# DAC.net
KiCad netlist of a schematic drawn in Altium Designer
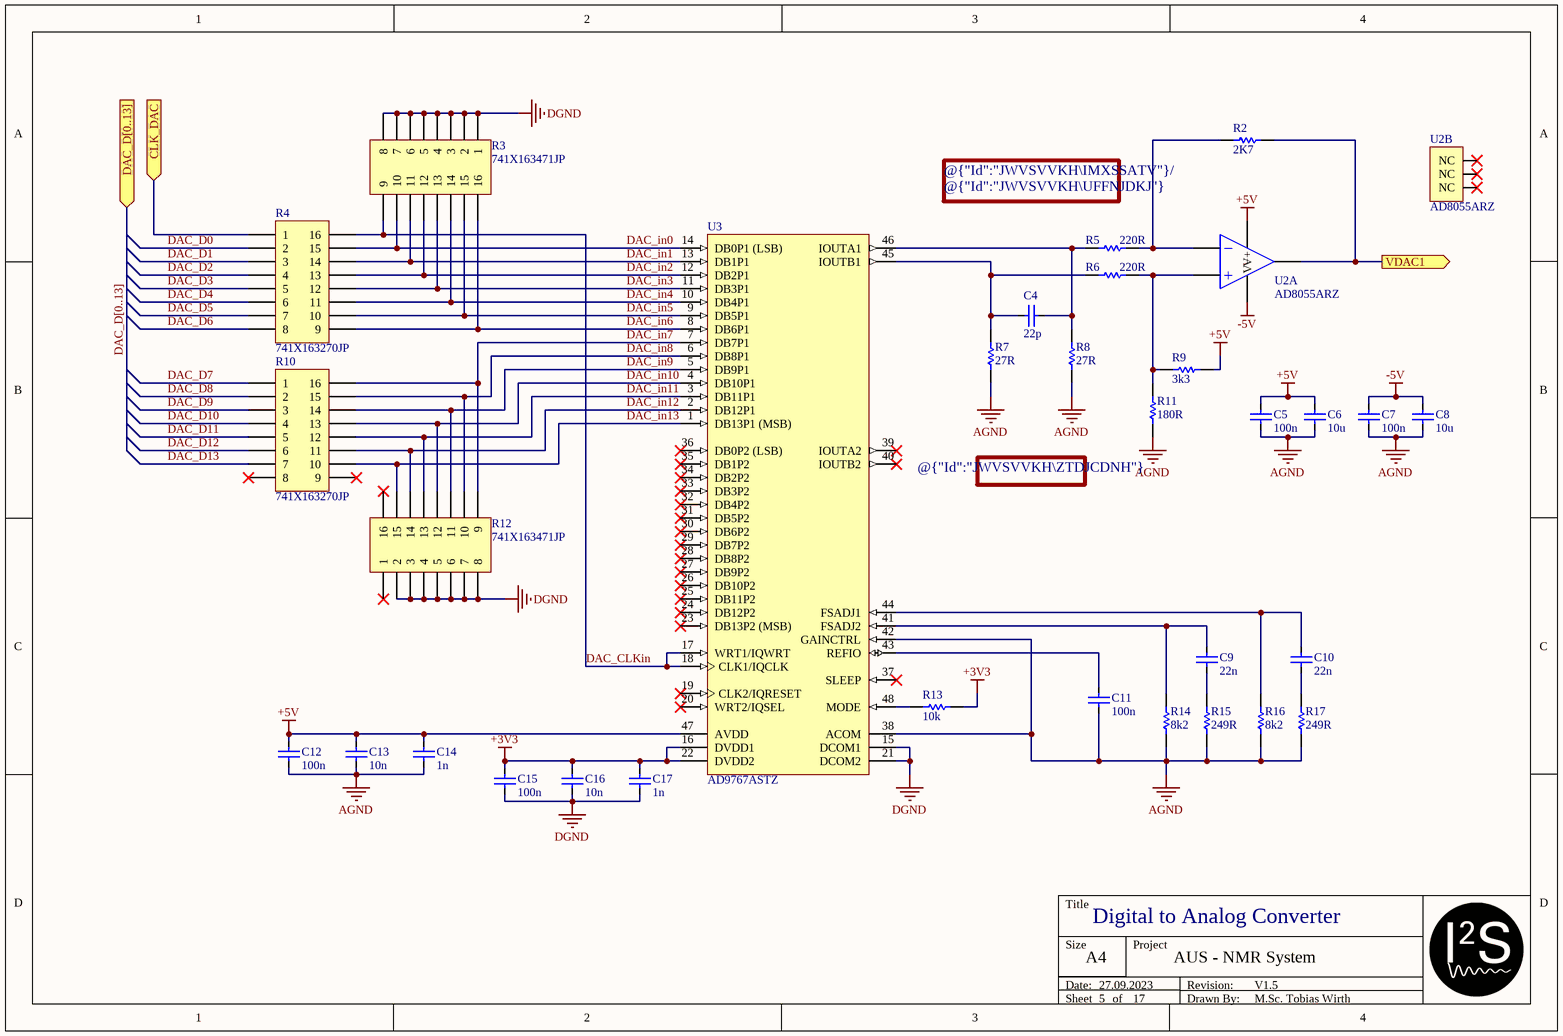
[diagram p0: DAC.SchDoc]

(export (version "E")
  (design (tool "Eeschema 10.0.6"))
  (components
    (comp (ref "C4") (value "22p") (footprint "CAP_0402") (libsource (lib "IIS-Lib_TW") (part "Cap")))
    (comp (ref "C5") (value "100n") (footprint "CAP_0402") (libsource (lib "IIS-Lib_TW") (part "Cap")))
    (comp (ref "C6") (value "10u") (footprint "CAP_0603") (libsource (lib "IIS-Lib_TW") (part "Cap")))
    (comp (ref "C7") (value "100n") (footprint "CAP_0402") (libsource (lib "IIS-Lib_TW") (part "Cap")))
    (comp (ref "C8") (value "10u") (footprint "CAP_0603") (libsource (lib "IIS-Lib_TW") (part "Cap")))
    (comp (ref "C9") (value "22n") (footprint "CAP_0402") (libsource (lib "IIS-Lib_TW") (part "Cap")))
    (comp (ref "C10") (value "22n") (footprint "CAP_0402") (libsource (lib "IIS-Lib_TW") (part "Cap")))
    (comp (ref "C11") (value "100n") (footprint "CAP_0402") (libsource (lib "IIS-Lib_TW") (part "Cap")))
    (comp (ref "C12") (value "100n") (footprint "CAP_0402") (libsource (lib "IIS-Lib_TW") (part "Cap")))
    (comp (ref "C13") (value "10n") (footprint "CAP_0402") (libsource (lib "IIS-Lib_TW") (part "Cap")))
    (comp (ref "C14") (value "1n") (footprint "CAP_0402") (libsource (lib "IIS-Lib_TW") (part "Cap")))
    (comp (ref "C15") (value "100n") (footprint "CAP_0402") (libsource (lib "IIS-Lib_TW") (part "Cap")))
    (comp (ref "C16") (value "10n") (footprint "CAP_0402") (libsource (lib "IIS-Lib_TW") (part "Cap")))
    (comp (ref "C17") (value "1n") (footprint "CAP_0402") (libsource (lib "IIS-Lib_TW") (part "Cap")))
    (comp (ref "R2") (value "2K7") (footprint "RES_0402") (libsource (lib "IIS-Lib_TW") (part "Res")))
    (comp (ref "R3")
      (value "741X163471JP")
      (footprint "741X163")
      (description "Isolated 8 Resistor Network/Array, Convex, Long Side Terminals")
      (libsource (lib "") (part "741X163_2"))
    )
    (comp (ref "R4")
      (value "741X163270JP")
      (footprint "741X163")
      (description "Isolated 8 Resistor Network/Array, Convex, Long Side Terminals")
      (libsource (lib "IIS-Lib_TW") (part "741X163"))
    )
    (comp (ref "R5") (value "220R") (footprint "RES_0402") (libsource (lib "IIS-Lib_TW") (part "Res")))
    (comp (ref "R6") (value "220R") (footprint "RES_0402") (libsource (lib "IIS-Lib_TW") (part "Res")))
    (comp (ref "R7") (value "27R") (footprint "RES_0402") (libsource (lib "IIS-Lib_TW") (part "Res")))
    (comp (ref "R8") (value "27R") (footprint "RES_0402") (libsource (lib "IIS-Lib_TW") (part "Res")))
    (comp (ref "R9") (value "3k3") (footprint "RES_0402") (libsource (lib "IIS-Lib_TW") (part "Res")))
    (comp (ref "R10")
      (value "741X163270JP")
      (footprint "741X163")
      (description "Isolated 8 Resistor Network/Array, Convex, Long Side Terminals")
      (libsource (lib "IIS-Lib_TW") (part "741X163"))
    )
    (comp (ref "R11") (value "180R") (footprint "RES_0402") (libsource (lib "IIS-Lib_TW") (part "Res")))
    (comp (ref "R12")
      (value "741X163471JP")
      (footprint "741X163")
      (description "Isolated 8 Resistor Network/Array, Convex, Long Side Terminals")
      (libsource (lib "") (part "741X163_1"))
    )
    (comp (ref "R13") (value "10k") (footprint "RES_0402") (libsource (lib "IIS-Lib_TW") (part "Res")))
    (comp (ref "R14") (value "8k2") (footprint "RES_0402") (libsource (lib "IIS-Lib_TW") (part "Res")))
    (comp (ref "R15") (value "249R") (footprint "RES_0402") (libsource (lib "IIS-Lib_TW") (part "Res")))
    (comp (ref "R16") (value "8k2") (footprint "RES_0402") (libsource (lib "IIS-Lib_TW") (part "Res")))
    (comp (ref "R17") (value "249R") (footprint "RES_0402") (libsource (lib "IIS-Lib_TW") (part "Res")))
    (comp (ref "U2")
      (value "AD8055ARZ")
      (footprint "SOIC127P600X175-8N")
      (description "300 MHz Voltage Feedback Amplifier")
      (libsource (lib "IIS-Lib_TW") (part "AD8055"))
    )
    (comp (ref "U3")
      (value "AD9767ASTZ")
      (footprint "TQFP-48_L")
      (description "Dual 14-Bit TxDAC+, 125 Msps, -40 to +85 degC, ST-48, Pb-Free, Tray")
      (fields (field (name "GENERIC PART NUMBER") "AD9767") (field (name "MANUFACTURER") "Analog Devices"))
      (libsource (lib "IIS-Lib_TW") (part "AD9767"))
    )
  )
  (nets
    (net (code "1") (name "+3V3") (class "Default")
      (node (ref "C15") (pin "1") (pinfunction "1_1") (pintype "passive"))
      (node (ref "C16") (pin "1") (pinfunction "1_1") (pintype "passive"))
      (node (ref "C17") (pin "1") (pinfunction "1_1") (pintype "passive"))
      (node (ref "R13") (pin "1") (pinfunction "1_1") (pintype "passive"))
      (node (ref "U3") (pin "16") (pinfunction "DVDD1_16") (pintype "power_in"))
      (node (ref "U3") (pin "22") (pinfunction "DVDD2_22") (pintype "power_in"))
    )
    (net (code "2") (name "+5V") (class "Default")
      (node (ref "C12") (pin "1") (pinfunction "1_1") (pintype "passive"))
      (node (ref "C13") (pin "1") (pinfunction "1_1") (pintype "passive"))
      (node (ref "C14") (pin "1") (pinfunction "1_1") (pintype "passive"))
      (node (ref "C5") (pin "1") (pinfunction "1_1") (pintype "passive"))
      (node (ref "C6") (pin "1") (pinfunction "1_1") (pintype "passive"))
      (node (ref "R9") (pin "1") (pinfunction "1_1") (pintype "passive"))
      (node (ref "U2") (pin "7") (pinfunction "V+_7") (pintype "passive"))
      (node (ref "U3") (pin "47") (pinfunction "AVDD_47") (pintype "power_in"))
    )
    (net (code "3") (name "-5V") (class "Default")
      (node (ref "C7") (pin "1") (pinfunction "1_1") (pintype "passive"))
      (node (ref "C8") (pin "1") (pinfunction "1_1") (pintype "passive"))
      (node (ref "U2") (pin "4") (pinfunction "V−_4") (pintype "passive"))
    )
    (net (code "5") (name "/CLK_DAC") (class "Default")
      (node (ref "R4") (pin "1") (pinfunction "1_1") (pintype "passive"))
    )
    (net (code "6") (name "/DAC_CLKin") (class "Default")
      (node (ref "R3") (pin "9") (pinfunction "9_9") (pintype "passive"))
      (node (ref "R4") (pin "16") (pinfunction "16_16") (pintype "passive"))
      (node (ref "U3") (pin "17") (pinfunction "WRT1/IQWRT_17") (pintype "input"))
      (node (ref "U3") (pin "18") (pinfunction "CLK1/IQCLK_18") (pintype "input"))
    )
    (net (code "7") (name "/DAC_D0") (class "Default")
      (node (ref "R4") (pin "2") (pinfunction "2_2") (pintype "passive"))
    )
    (net (code "8") (name "/DAC_D1") (class "Default")
      (node (ref "R4") (pin "3") (pinfunction "3_3") (pintype "passive"))
    )
    (net (code "9") (name "/DAC_D2") (class "Default")
      (node (ref "R4") (pin "4") (pinfunction "4_4") (pintype "passive"))
    )
    (net (code "10") (name "/DAC_D3") (class "Default")
      (node (ref "R4") (pin "5") (pinfunction "5_5") (pintype "passive"))
    )
    (net (code "11") (name "/DAC_D4") (class "Default")
      (node (ref "R4") (pin "6") (pinfunction "6_6") (pintype "passive"))
    )
    (net (code "12") (name "/DAC_D5") (class "Default")
      (node (ref "R4") (pin "7") (pinfunction "7_7") (pintype "passive"))
    )
    (net (code "13") (name "/DAC_D6") (class "Default")
      (node (ref "R4") (pin "8") (pinfunction "8_8") (pintype "passive"))
    )
    (net (code "14") (name "/DAC_D7") (class "Default")
      (node (ref "R10") (pin "1") (pinfunction "1_1") (pintype "passive"))
    )
    (net (code "15") (name "/DAC_D8") (class "Default")
      (node (ref "R10") (pin "2") (pinfunction "2_2") (pintype "passive"))
    )
    (net (code "16") (name "/DAC_D9") (class "Default")
      (node (ref "R10") (pin "3") (pinfunction "3_3") (pintype "passive"))
    )
    (net (code "17") (name "/DAC_D10") (class "Default")
      (node (ref "R10") (pin "4") (pinfunction "4_4") (pintype "passive"))
    )
    (net (code "18") (name "/DAC_D11") (class "Default")
      (node (ref "R10") (pin "5") (pinfunction "5_5") (pintype "passive"))
    )
    (net (code "19") (name "/DAC_D12") (class "Default")
      (node (ref "R10") (pin "6") (pinfunction "6_6") (pintype "passive"))
    )
    (net (code "20") (name "/DAC_D13") (class "Default")
      (node (ref "R10") (pin "7") (pinfunction "7_7") (pintype "passive"))
    )
    (net (code "22") (name "/DAC_in0") (class "Default")
      (node (ref "R3") (pin "10") (pinfunction "10_10") (pintype "passive"))
      (node (ref "R4") (pin "15") (pinfunction "15_15") (pintype "passive"))
      (node (ref "U3") (pin "14") (pinfunction "DB0P1_(LSB)_14") (pintype "input"))
    )
    (net (code "23") (name "/DAC_in1") (class "Default")
      (node (ref "R3") (pin "11") (pinfunction "11_11") (pintype "passive"))
      (node (ref "R4") (pin "14") (pinfunction "14_14") (pintype "passive"))
      (node (ref "U3") (pin "13") (pinfunction "DB1P1_13") (pintype "input"))
    )
    (net (code "24") (name "/DAC_in2") (class "Default")
      (node (ref "R3") (pin "12") (pinfunction "12_12") (pintype "passive"))
      (node (ref "R4") (pin "13") (pinfunction "13_13") (pintype "passive"))
      (node (ref "U3") (pin "12") (pinfunction "DB2P1_12") (pintype "input"))
    )
    (net (code "25") (name "/DAC_in3") (class "Default")
      (node (ref "R3") (pin "13") (pinfunction "13_13") (pintype "passive"))
      (node (ref "R4") (pin "12") (pinfunction "12_12") (pintype "passive"))
      (node (ref "U3") (pin "11") (pinfunction "DB3P1_11") (pintype "input"))
    )
    (net (code "26") (name "/DAC_in4") (class "Default")
      (node (ref "R3") (pin "14") (pinfunction "14_14") (pintype "passive"))
      (node (ref "R4") (pin "11") (pinfunction "11_11") (pintype "passive"))
      (node (ref "U3") (pin "10") (pinfunction "DB4P1_10") (pintype "input"))
    )
    (net (code "27") (name "/DAC_in5") (class "Default")
      (node (ref "R3") (pin "15") (pinfunction "15_15") (pintype "passive"))
      (node (ref "R4") (pin "10") (pinfunction "10_10") (pintype "passive"))
      (node (ref "U3") (pin "9") (pinfunction "DB5P1_9") (pintype "input"))
    )
    (net (code "28") (name "/DAC_in6") (class "Default")
      (node (ref "R3") (pin "16") (pinfunction "16_16") (pintype "passive"))
      (node (ref "R4") (pin "9") (pinfunction "9_9") (pintype "passive"))
      (node (ref "U3") (pin "8") (pinfunction "DB6P1_8") (pintype "input"))
    )
    (net (code "29") (name "/DAC_in7") (class "Default")
      (node (ref "R10") (pin "16") (pinfunction "16_16") (pintype "passive"))
      (node (ref "R12") (pin "9") (pinfunction "9_9") (pintype "passive"))
      (node (ref "U3") (pin "7") (pinfunction "DB7P1_7") (pintype "input"))
    )
    (net (code "30") (name "/DAC_in8") (class "Default")
      (node (ref "R10") (pin "15") (pinfunction "15_15") (pintype "passive"))
      (node (ref "R12") (pin "10") (pinfunction "10_10") (pintype "passive"))
      (node (ref "U3") (pin "6") (pinfunction "DB8P1_6") (pintype "input"))
    )
    (net (code "31") (name "/DAC_in9") (class "Default")
      (node (ref "R10") (pin "14") (pinfunction "14_14") (pintype "passive"))
      (node (ref "R12") (pin "11") (pinfunction "11_11") (pintype "passive"))
      (node (ref "U3") (pin "5") (pinfunction "DB9P1_5") (pintype "input"))
    )
    (net (code "32") (name "/DAC_in10") (class "Default")
      (node (ref "R10") (pin "13") (pinfunction "13_13") (pintype "passive"))
      (node (ref "R12") (pin "12") (pinfunction "12_12") (pintype "passive"))
      (node (ref "U3") (pin "4") (pinfunction "DB10P1_4") (pintype "input"))
    )
    (net (code "33") (name "/DAC_in11") (class "Default")
      (node (ref "R10") (pin "12") (pinfunction "12_12") (pintype "passive"))
      (node (ref "R12") (pin "13") (pinfunction "13_13") (pintype "passive"))
      (node (ref "U3") (pin "3") (pinfunction "DB11P1_3") (pintype "input"))
    )
    (net (code "34") (name "/DAC_in12") (class "Default")
      (node (ref "R10") (pin "11") (pinfunction "11_11") (pintype "passive"))
      (node (ref "R12") (pin "14") (pinfunction "14_14") (pintype "passive"))
      (node (ref "U3") (pin "2") (pinfunction "DB12P1_2") (pintype "input"))
    )
    (net (code "35") (name "/DAC_in13") (class "Default")
      (node (ref "R10") (pin "10") (pinfunction "10_10") (pintype "passive"))
      (node (ref "R12") (pin "15") (pinfunction "15_15") (pintype "passive"))
      (node (ref "U3") (pin "1") (pinfunction "DB13P1_(MSB)_1") (pintype "input"))
    )
    (net (code "36") (name "/VDAC1") (class "Default")
      (node (ref "R2") (pin "2") (pinfunction "2_2") (pintype "passive"))
      (node (ref "U2") (pin "6") (pinfunction "6_6") (pintype "passive"))
    )
    (net (code "37") (name "AGND") (class "Default")
      (node (ref "C11") (pin "2") (pinfunction "2_2") (pintype "passive"))
      (node (ref "C12") (pin "2") (pinfunction "2_2") (pintype "passive"))
      (node (ref "C13") (pin "2") (pinfunction "2_2") (pintype "passive"))
      (node (ref "C14") (pin "2") (pinfunction "2_2") (pintype "passive"))
      (node (ref "C5") (pin "2") (pinfunction "2_2") (pintype "passive"))
      (node (ref "C6") (pin "2") (pinfunction "2_2") (pintype "passive"))
      (node (ref "C7") (pin "2") (pinfunction "2_2") (pintype "passive"))
      (node (ref "C8") (pin "2") (pinfunction "2_2") (pintype "passive"))
      (node (ref "R11") (pin "1") (pinfunction "1_1") (pintype "passive"))
      (node (ref "R14") (pin "1") (pinfunction "1_1") (pintype "passive"))
      (node (ref "R15") (pin "1") (pinfunction "1_1") (pintype "passive"))
      (node (ref "R16") (pin "1") (pinfunction "1_1") (pintype "passive"))
      (node (ref "R17") (pin "1") (pinfunction "1_1") (pintype "passive"))
      (node (ref "R7") (pin "1") (pinfunction "1_1") (pintype "passive"))
      (node (ref "R8") (pin "1") (pinfunction "1_1") (pintype "passive"))
      (node (ref "U3") (pin "38") (pinfunction "ACOM_38") (pintype "power_in"))
      (node (ref "U3") (pin "42") (pinfunction "GAINCTRL_42") (pintype "input"))
    )
    (net (code "38") (name "DGND") (class "Default")
      (node (ref "C15") (pin "2") (pinfunction "2_2") (pintype "passive"))
      (node (ref "C16") (pin "2") (pinfunction "2_2") (pintype "passive"))
      (node (ref "C17") (pin "2") (pinfunction "2_2") (pintype "passive"))
      (node (ref "R12") (pin "2") (pinfunction "2_2") (pintype "passive"))
      (node (ref "R12") (pin "3") (pinfunction "3_3") (pintype "passive"))
      (node (ref "R12") (pin "4") (pinfunction "4_4") (pintype "passive"))
      (node (ref "R12") (pin "5") (pinfunction "5_5") (pintype "passive"))
      (node (ref "R12") (pin "6") (pinfunction "6_6") (pintype "passive"))
      (node (ref "R12") (pin "7") (pinfunction "7_7") (pintype "passive"))
      (node (ref "R12") (pin "8") (pinfunction "8_8") (pintype "passive"))
      (node (ref "R3") (pin "1") (pinfunction "1_1") (pintype "passive"))
      (node (ref "R3") (pin "2") (pinfunction "2_2") (pintype "passive"))
      (node (ref "R3") (pin "3") (pinfunction "3_3") (pintype "passive"))
      (node (ref "R3") (pin "4") (pinfunction "4_4") (pintype "passive"))
      (node (ref "R3") (pin "5") (pinfunction "5_5") (pintype "passive"))
      (node (ref "R3") (pin "6") (pinfunction "6_6") (pintype "passive"))
      (node (ref "R3") (pin "7") (pinfunction "7_7") (pintype "passive"))
      (node (ref "R3") (pin "8") (pinfunction "8_8") (pintype "passive"))
      (node (ref "U3") (pin "15") (pinfunction "DCOM1_15") (pintype "power_in"))
      (node (ref "U3") (pin "21") (pinfunction "DCOM2_21") (pintype "power_in"))
    )
    (net (code "39") (name "Net-(C9-Pad2)") (class "Default")
      (node (ref "C9") (pin "2") (pinfunction "2_2") (pintype "passive"))
      (node (ref "R15") (pin "2") (pinfunction "2_2") (pintype "passive"))
    )
    (net (code "40") (name "Net-(C10-Pad2)") (class "Default")
      (node (ref "C10") (pin "2") (pinfunction "2_2") (pintype "passive"))
      (node (ref "R17") (pin "2") (pinfunction "2_2") (pintype "passive"))
    )
    (net (code "41") (name "Net-(U2A-+)") (class "Default")
      (node (ref "R11") (pin "2") (pinfunction "2_2") (pintype "passive"))
      (node (ref "R6") (pin "1") (pinfunction "1_1") (pintype "passive"))
      (node (ref "R9") (pin "2") (pinfunction "2_2") (pintype "passive"))
      (node (ref "U2") (pin "3") (pinfunction "+_3") (pintype "passive"))
    )
    (net (code "42") (name "Net-(U2A-−)") (class "Default")
      (node (ref "R2") (pin "1") (pinfunction "1_1") (pintype "passive"))
      (node (ref "R5") (pin "1") (pinfunction "1_1") (pintype "passive"))
      (node (ref "U2") (pin "2") (pinfunction "−_2") (pintype "passive"))
    )
    (net (code "43") (name "Net-(U3-FSADJ1)") (class "Default")
      (node (ref "C10") (pin "1") (pinfunction "1_1") (pintype "passive"))
      (node (ref "R16") (pin "2") (pinfunction "2_2") (pintype "passive"))
      (node (ref "U3") (pin "44") (pinfunction "FSADJ1_44") (pintype "input"))
    )
    (net (code "44") (name "Net-(U3-FSADJ2)") (class "Default")
      (node (ref "C9") (pin "1") (pinfunction "1_1") (pintype "passive"))
      (node (ref "R14") (pin "2") (pinfunction "2_2") (pintype "passive"))
      (node (ref "U3") (pin "41") (pinfunction "FSADJ2_41") (pintype "input"))
    )
    (net (code "45") (name "Net-(U3-IOUTA1)") (class "Default")
      (node (ref "C4") (pin "1") (pinfunction "1_1") (pintype "passive"))
      (node (ref "R5") (pin "2") (pinfunction "2_2") (pintype "passive"))
      (node (ref "R8") (pin "2") (pinfunction "2_2") (pintype "passive"))
      (node (ref "U3") (pin "46") (pinfunction "IOUTA1_46") (pintype "output"))
    )
    (net (code "46") (name "Net-(U3-IOUTB1)") (class "Default")
      (node (ref "C4") (pin "2") (pinfunction "2_2") (pintype "passive"))
      (node (ref "R6") (pin "2") (pinfunction "2_2") (pintype "passive"))
      (node (ref "R7") (pin "2") (pinfunction "2_2") (pintype "passive"))
      (node (ref "U3") (pin "45") (pinfunction "IOUTB1_45") (pintype "output"))
    )
    (net (code "47") (name "Net-(U3-MODE)") (class "Default")
      (node (ref "R13") (pin "2") (pinfunction "2_2") (pintype "passive"))
      (node (ref "U3") (pin "48") (pinfunction "MODE_48") (pintype "input"))
    )
    (net (code "48") (name "Net-(U3-REFIO)") (class "Default")
      (node (ref "C11") (pin "1") (pinfunction "1_1") (pintype "passive"))
      (node (ref "U3") (pin "43") (pinfunction "REFIO_43") (pintype "bidirectional"))
    )
    (net (code "49") (name "unconnected-(R10-Pad8)") (class "Default")
      (node (ref "R10") (pin "8") (pinfunction "8_8") (pintype "passive+no_connect"))
    )
    (net (code "50") (name "unconnected-(R10-Pad9)") (class "Default")
      (node (ref "R10") (pin "9") (pinfunction "9_9") (pintype "passive+no_connect"))
    )
    (net (code "51") (name "unconnected-(R12-Pad1)") (class "Default")
      (node (ref "R12") (pin "1") (pinfunction "1_1") (pintype "passive+no_connect"))
    )
    (net (code "52") (name "unconnected-(R12-Pad16)") (class "Default")
      (node (ref "R12") (pin "16") (pinfunction "16_16") (pintype "passive+no_connect"))
    )
    (net (code "53") (name "unconnected-(U2B-NC-Pad1)") (class "Default")
      (node (ref "U2") (pin "1") (pinfunction "NC_1") (pintype "passive+no_connect"))
    )
    (net (code "54") (name "unconnected-(U2B-NC-Pad5)") (class "Default")
      (node (ref "U2") (pin "5") (pinfunction "NC_5") (pintype "passive+no_connect"))
    )
    (net (code "55") (name "unconnected-(U2B-NC-Pad8)") (class "Default")
      (node (ref "U2") (pin "8") (pinfunction "NC_8") (pintype "passive+no_connect"))
    )
    (net (code "56") (name "unconnected-(U3-CLK2{slash}IQRESET-Pad19)") (class "Default")
      (node (ref "U3") (pin "19") (pinfunction "CLK2/IQRESET_19") (pintype "input+no_connect"))
    )
    (net (code "57") (name "unconnected-(U3-DB0P2_(LSB)-Pad36)") (class "Default")
      (node (ref "U3") (pin "36") (pinfunction "DB0P2_(LSB)_36") (pintype "input+no_connect"))
    )
    (net (code "58") (name "unconnected-(U3-DB1P2-Pad35)") (class "Default")
      (node (ref "U3") (pin "35") (pinfunction "DB1P2_35") (pintype "input+no_connect"))
    )
    (net (code "59") (name "unconnected-(U3-DB2P2-Pad34)") (class "Default")
      (node (ref "U3") (pin "34") (pinfunction "DB2P2_34") (pintype "input+no_connect"))
    )
    (net (code "60") (name "unconnected-(U3-DB3P2-Pad33)") (class "Default")
      (node (ref "U3") (pin "33") (pinfunction "DB3P2_33") (pintype "input+no_connect"))
    )
    (net (code "61") (name "unconnected-(U3-DB4P2-Pad32)") (class "Default")
      (node (ref "U3") (pin "32") (pinfunction "DB4P2_32") (pintype "input+no_connect"))
    )
    (net (code "62") (name "unconnected-(U3-DB5P2-Pad31)") (class "Default")
      (node (ref "U3") (pin "31") (pinfunction "DB5P2_31") (pintype "input+no_connect"))
    )
    (net (code "63") (name "unconnected-(U3-DB6P2-Pad30)") (class "Default")
      (node (ref "U3") (pin "30") (pinfunction "DB6P2_30") (pintype "input+no_connect"))
    )
    (net (code "64") (name "unconnected-(U3-DB7P2-Pad29)") (class "Default")
      (node (ref "U3") (pin "29") (pinfunction "DB7P2_29") (pintype "input+no_connect"))
    )
    (net (code "65") (name "unconnected-(U3-DB8P2-Pad28)") (class "Default")
      (node (ref "U3") (pin "28") (pinfunction "DB8P2_28") (pintype "input+no_connect"))
    )
    (net (code "66") (name "unconnected-(U3-DB9P2-Pad27)") (class "Default")
      (node (ref "U3") (pin "27") (pinfunction "DB9P2_27") (pintype "input+no_connect"))
    )
    (net (code "67") (name "unconnected-(U3-DB10P2-Pad26)") (class "Default")
      (node (ref "U3") (pin "26") (pinfunction "DB10P2_26") (pintype "input+no_connect"))
    )
    (net (code "68") (name "unconnected-(U3-DB11P2-Pad25)") (class "Default")
      (node (ref "U3") (pin "25") (pinfunction "DB11P2_25") (pintype "input+no_connect"))
    )
    (net (code "69") (name "unconnected-(U3-DB12P2-Pad24)") (class "Default")
      (node (ref "U3") (pin "24") (pinfunction "DB12P2_24") (pintype "input+no_connect"))
    )
    (net (code "70") (name "unconnected-(U3-DB13P2_(MSB)-Pad23)") (class "Default")
      (node (ref "U3") (pin "23") (pinfunction "DB13P2_(MSB)_23") (pintype "input+no_connect"))
    )
    (net (code "71") (name "unconnected-(U3-IOUTA2-Pad39)") (class "Default")
      (node (ref "U3") (pin "39") (pinfunction "IOUTA2_39") (pintype "output+no_connect"))
    )
    (net (code "72") (name "unconnected-(U3-IOUTB2-Pad40)") (class "Default")
      (node (ref "U3") (pin "40") (pinfunction "IOUTB2_40") (pintype "output+no_connect"))
    )
    (net (code "73") (name "unconnected-(U3-SLEEP-Pad37)") (class "Default")
      (node (ref "U3") (pin "37") (pinfunction "SLEEP_37") (pintype "input+no_connect"))
    )
    (net (code "74") (name "unconnected-(U3-WRT2{slash}IQSEL-Pad20)") (class "Default")
      (node (ref "U3") (pin "20") (pinfunction "WRT2/IQSEL_20") (pintype "input+no_connect"))
    )
  )
)
